# Panel3.net
KiCad netlist of a schematic drawn in EAGLE
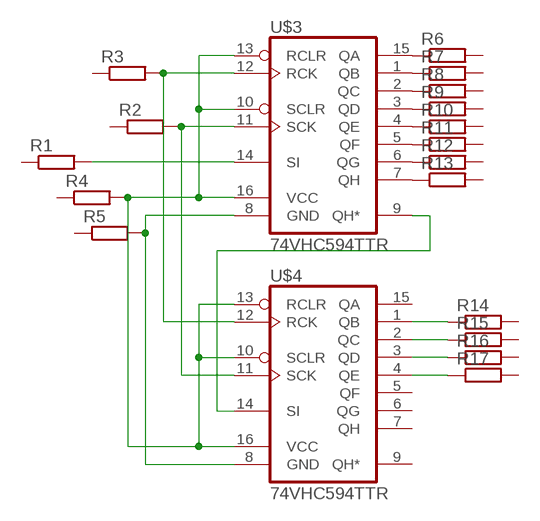
[diagram p0: schematic, sheet 1]

(export (version "E")
  (design (tool "Eeschema 10.0.6"))
  (components
    (comp (ref "R1")
      (value "R_0805")
      (footprint "eagle-import:R0805")
      (libsource (lib "eagle-import") (part "R_0805"))
    )
    (comp (ref "R2")
      (value "R_0805")
      (footprint "eagle-import:R0805")
      (libsource (lib "eagle-import") (part "R_0805"))
    )
    (comp (ref "R3")
      (value "R_0805")
      (footprint "eagle-import:R0805")
      (libsource (lib "eagle-import") (part "R_0805"))
    )
    (comp (ref "R4")
      (value "R_0805")
      (footprint "eagle-import:R0805")
      (libsource (lib "eagle-import") (part "R_0805"))
    )
    (comp (ref "R5")
      (value "R_0805")
      (footprint "eagle-import:R0805")
      (libsource (lib "eagle-import") (part "R_0805"))
    )
    (comp (ref "R6")
      (value "R_0805")
      (footprint "eagle-import:R0805")
      (libsource (lib "eagle-import") (part "R_0805"))
    )
    (comp (ref "R7")
      (value "R_0805")
      (footprint "eagle-import:R0805")
      (libsource (lib "eagle-import") (part "R_0805"))
    )
    (comp (ref "R8")
      (value "R_0805")
      (footprint "eagle-import:R0805")
      (libsource (lib "eagle-import") (part "R_0805"))
    )
    (comp (ref "R9")
      (value "R_0805")
      (footprint "eagle-import:R0805")
      (libsource (lib "eagle-import") (part "R_0805"))
    )
    (comp (ref "R10")
      (value "R_0805")
      (footprint "eagle-import:R0805")
      (libsource (lib "eagle-import") (part "R_0805"))
    )
    (comp (ref "R11")
      (value "R_0805")
      (footprint "eagle-import:R0805")
      (libsource (lib "eagle-import") (part "R_0805"))
    )
    (comp (ref "R12")
      (value "R_0805")
      (footprint "eagle-import:R0805")
      (libsource (lib "eagle-import") (part "R_0805"))
    )
    (comp (ref "R13")
      (value "R_0805")
      (footprint "eagle-import:R0805")
      (libsource (lib "eagle-import") (part "R_0805"))
    )
    (comp (ref "R14")
      (value "R_0805")
      (footprint "eagle-import:R0805")
      (libsource (lib "eagle-import") (part "R_0805"))
    )
    (comp (ref "R15")
      (value "R_0805")
      (footprint "eagle-import:R0805")
      (libsource (lib "eagle-import") (part "R_0805"))
    )
    (comp (ref "R16")
      (value "R_0805")
      (footprint "eagle-import:R0805")
      (libsource (lib "eagle-import") (part "R_0805"))
    )
    (comp (ref "R17")
      (value "R_0805")
      (footprint "eagle-import:R0805")
      (libsource (lib "eagle-import") (part "R_0805"))
    )
    (comp (ref "U$3")
      (value "74VHC594TTR")
      (footprint "eagle-import:TSSOP16")
      (libsource (lib "eagle-import") (part "74VHC594TTR"))
    )
    (comp (ref "U$4")
      (value "74VHC594TTR")
      (footprint "eagle-import:TSSOP16")
      (libsource (lib "eagle-import") (part "74VHC594TTR"))
    )
  )
  (nets
    (net (code "1") (name "Net-(U$3-GND)") (class "Default")
      (node (ref "R5") (pin "2") (pinfunction "2_2") (pintype "passive"))
      (node (ref "U$3") (pin "8") (pinfunction "GND_8") (pintype "bidirectional"))
      (node (ref "U$4") (pin "8") (pinfunction "GND_8") (pintype "bidirectional"))
    )
    (net (code "2") (name "Net-(U$3-QA)") (class "Default")
      (node (ref "R6") (pin "1") (pinfunction "1_1") (pintype "passive"))
      (node (ref "U$3") (pin "15") (pinfunction "QA_15") (pintype "output"))
    )
    (net (code "3") (name "Net-(U$3-QB)") (class "Default")
      (node (ref "R7") (pin "1") (pinfunction "1_1") (pintype "passive"))
      (node (ref "U$3") (pin "1") (pinfunction "QB_1") (pintype "output"))
    )
    (net (code "4") (name "Net-(U$3-QC)") (class "Default")
      (node (ref "R8") (pin "1") (pinfunction "1_1") (pintype "passive"))
      (node (ref "U$3") (pin "2") (pinfunction "QC_2") (pintype "output"))
    )
    (net (code "5") (name "Net-(U$3-QD)") (class "Default")
      (node (ref "R9") (pin "1") (pinfunction "1_1") (pintype "passive"))
      (node (ref "U$3") (pin "3") (pinfunction "QD_3") (pintype "output"))
    )
    (net (code "6") (name "Net-(U$3-QE)") (class "Default")
      (node (ref "R10") (pin "1") (pinfunction "1_1") (pintype "passive"))
      (node (ref "U$3") (pin "4") (pinfunction "QE_4") (pintype "output"))
    )
    (net (code "7") (name "Net-(U$3-QF)") (class "Default")
      (node (ref "R11") (pin "1") (pinfunction "1_1") (pintype "passive"))
      (node (ref "U$3") (pin "5") (pinfunction "QF_5") (pintype "output"))
    )
    (net (code "8") (name "Net-(U$3-QG)") (class "Default")
      (node (ref "R12") (pin "1") (pinfunction "1_1") (pintype "passive"))
      (node (ref "U$3") (pin "6") (pinfunction "QG_6") (pintype "output"))
    )
    (net (code "9") (name "Net-(U$3-QH)") (class "Default")
      (node (ref "R13") (pin "1") (pinfunction "1_1") (pintype "passive"))
      (node (ref "U$3") (pin "7") (pinfunction "QH_7") (pintype "output"))
    )
    (net (code "10") (name "Net-(U$3-QH*)") (class "Default")
      (node (ref "U$3") (pin "9") (pinfunction "QH*_9") (pintype "output"))
      (node (ref "U$4") (pin "14") (pinfunction "SI_14") (pintype "input"))
    )
    (net (code "11") (name "Net-(U$3-RCK)") (class "Default")
      (node (ref "R3") (pin "2") (pinfunction "2_2") (pintype "passive"))
      (node (ref "U$3") (pin "12") (pinfunction "RCK_12") (pintype "input"))
      (node (ref "U$4") (pin "12") (pinfunction "RCK_12") (pintype "input"))
    )
    (net (code "12") (name "Net-(U$3-RCLR)") (class "Default")
      (node (ref "R4") (pin "2") (pinfunction "2_2") (pintype "passive"))
      (node (ref "U$3") (pin "10") (pinfunction "SCLR_10") (pintype "input"))
      (node (ref "U$3") (pin "13") (pinfunction "RCLR_13") (pintype "input"))
      (node (ref "U$3") (pin "16") (pinfunction "VCC_16") (pintype "bidirectional"))
      (node (ref "U$4") (pin "10") (pinfunction "SCLR_10") (pintype "input"))
      (node (ref "U$4") (pin "13") (pinfunction "RCLR_13") (pintype "input"))
      (node (ref "U$4") (pin "16") (pinfunction "VCC_16") (pintype "bidirectional"))
    )
    (net (code "13") (name "Net-(U$3-SCK)") (class "Default")
      (node (ref "R2") (pin "2") (pinfunction "2_2") (pintype "passive"))
      (node (ref "U$3") (pin "11") (pinfunction "SCK_11") (pintype "input"))
      (node (ref "U$4") (pin "11") (pinfunction "SCK_11") (pintype "input"))
    )
    (net (code "14") (name "Net-(U$3-SI)") (class "Default")
      (node (ref "R1") (pin "2") (pinfunction "2_2") (pintype "passive"))
      (node (ref "U$3") (pin "14") (pinfunction "SI_14") (pintype "input"))
    )
    (net (code "15") (name "Net-(U$4-QB)") (class "Default")
      (node (ref "R14") (pin "1") (pinfunction "1_1") (pintype "passive"))
      (node (ref "U$4") (pin "1") (pinfunction "QB_1") (pintype "output"))
    )
    (net (code "16") (name "Net-(U$4-QC)") (class "Default")
      (node (ref "R15") (pin "1") (pinfunction "1_1") (pintype "passive"))
      (node (ref "U$4") (pin "2") (pinfunction "QC_2") (pintype "output"))
    )
    (net (code "17") (name "Net-(U$4-QD)") (class "Default")
      (node (ref "R16") (pin "1") (pinfunction "1_1") (pintype "passive"))
      (node (ref "U$4") (pin "3") (pinfunction "QD_3") (pintype "output"))
    )
    (net (code "18") (name "Net-(U$4-QE)") (class "Default")
      (node (ref "R17") (pin "1") (pinfunction "1_1") (pintype "passive"))
      (node (ref "U$4") (pin "4") (pinfunction "QE_4") (pintype "output"))
    )
    (net (code "19") (name "unconnected-(R1-Pad1)") (class "Default")
      (node (ref "R1") (pin "1") (pinfunction "1_1") (pintype "passive"))
    )
    (net (code "20") (name "unconnected-(R2-Pad1)") (class "Default")
      (node (ref "R2") (pin "1") (pinfunction "1_1") (pintype "passive"))
    )
    (net (code "21") (name "unconnected-(R3-Pad1)") (class "Default")
      (node (ref "R3") (pin "1") (pinfunction "1_1") (pintype "passive"))
    )
    (net (code "22") (name "unconnected-(R4-Pad1)") (class "Default")
      (node (ref "R4") (pin "1") (pinfunction "1_1") (pintype "passive"))
    )
    (net (code "23") (name "unconnected-(R5-Pad1)") (class "Default")
      (node (ref "R5") (pin "1") (pinfunction "1_1") (pintype "passive"))
    )
    (net (code "24") (name "unconnected-(R6-Pad2)") (class "Default")
      (node (ref "R6") (pin "2") (pinfunction "2_2") (pintype "passive"))
    )
    (net (code "25") (name "unconnected-(R7-Pad2)") (class "Default")
      (node (ref "R7") (pin "2") (pinfunction "2_2") (pintype "passive"))
    )
    (net (code "26") (name "unconnected-(R8-Pad2)") (class "Default")
      (node (ref "R8") (pin "2") (pinfunction "2_2") (pintype "passive"))
    )
    (net (code "27") (name "unconnected-(R9-Pad2)") (class "Default")
      (node (ref "R9") (pin "2") (pinfunction "2_2") (pintype "passive"))
    )
    (net (code "28") (name "unconnected-(R10-Pad2)") (class "Default")
      (node (ref "R10") (pin "2") (pinfunction "2_2") (pintype "passive"))
    )
    (net (code "29") (name "unconnected-(R11-Pad2)") (class "Default")
      (node (ref "R11") (pin "2") (pinfunction "2_2") (pintype "passive"))
    )
    (net (code "30") (name "unconnected-(R12-Pad2)") (class "Default")
      (node (ref "R12") (pin "2") (pinfunction "2_2") (pintype "passive"))
    )
    (net (code "31") (name "unconnected-(R13-Pad2)") (class "Default")
      (node (ref "R13") (pin "2") (pinfunction "2_2") (pintype "passive"))
    )
    (net (code "32") (name "unconnected-(R14-Pad2)") (class "Default")
      (node (ref "R14") (pin "2") (pinfunction "2_2") (pintype "passive"))
    )
    (net (code "33") (name "unconnected-(R15-Pad2)") (class "Default")
      (node (ref "R15") (pin "2") (pinfunction "2_2") (pintype "passive"))
    )
    (net (code "34") (name "unconnected-(R16-Pad2)") (class "Default")
      (node (ref "R16") (pin "2") (pinfunction "2_2") (pintype "passive"))
    )
    (net (code "35") (name "unconnected-(R17-Pad2)") (class "Default")
      (node (ref "R17") (pin "2") (pinfunction "2_2") (pintype "passive"))
    )
    (net (code "36") (name "unconnected-(U$4-QA-Pad15)") (class "Default")
      (node (ref "U$4") (pin "15") (pinfunction "QA_15") (pintype "output"))
    )
    (net (code "37") (name "unconnected-(U$4-QF-Pad5)") (class "Default")
      (node (ref "U$4") (pin "5") (pinfunction "QF_5") (pintype "output"))
    )
    (net (code "38") (name "unconnected-(U$4-QG-Pad6)") (class "Default")
      (node (ref "U$4") (pin "6") (pinfunction "QG_6") (pintype "output"))
    )
    (net (code "39") (name "unconnected-(U$4-QH*-Pad9)") (class "Default")
      (node (ref "U$4") (pin "9") (pinfunction "QH*_9") (pintype "output"))
    )
    (net (code "40") (name "unconnected-(U$4-QH-Pad7)") (class "Default")
      (node (ref "U$4") (pin "7") (pinfunction "QH_7") (pintype "output"))
    )
  )
)
